# 3EWL1-200001_02.net
KiCad netlist of a schematic drawn in Altium Designer
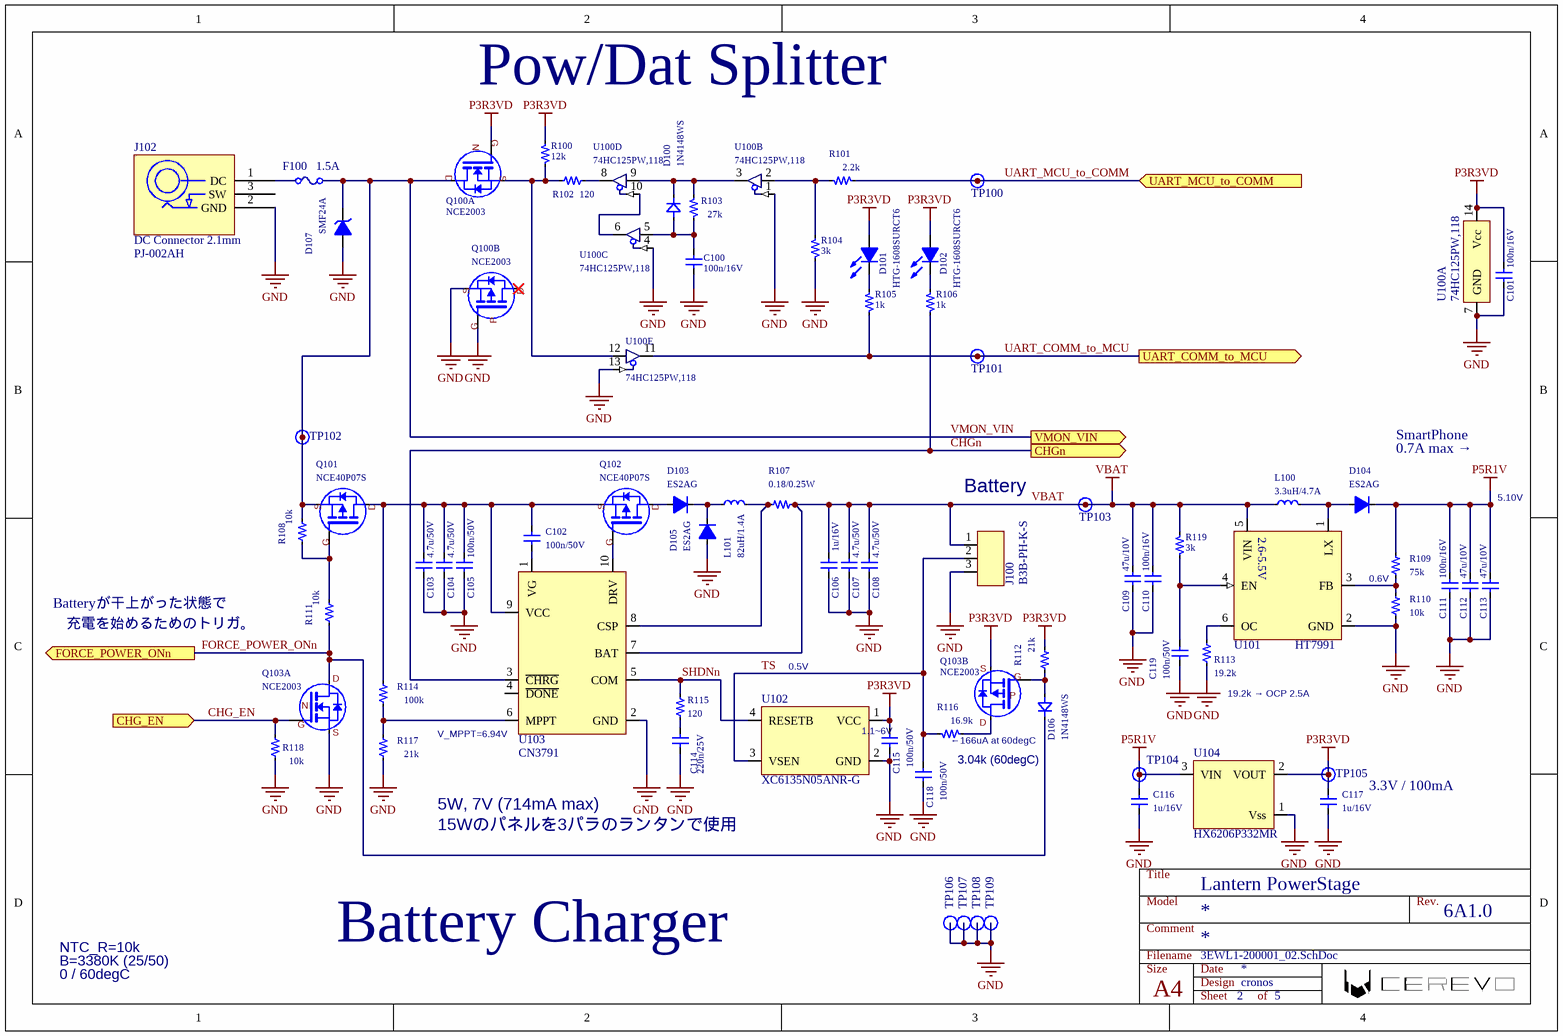
[diagram p0: 3EWL1-200001_02.SchDoc]

(export (version "E")
  (design (tool "Eeschema 10.0.6"))
  (components
    (comp (ref "C100")
      (value "100n/16V")
      (footprint "SC2-1.00X0.50A")
      (description "100n, 16V, X7R, 1005Size")
      (fields
        (field (name "MANUFACTURER") "TDK")
        (field (name "MANUFACTURER PART NUMBER") "C1005X5R1C104KT000N")
      )
      (libsource (lib "I_Lib_cronos_NewLayer") (part "C"))
    )
    (comp (ref "C101")
      (value "100n/16V")
      (footprint "SC2-1.00X0.50A")
      (description "100n, 16V, X7R, 1005Size")
      (fields
        (field (name "MANUFACTURER") "TDK")
        (field (name "MANUFACTURER PART NUMBER") "C1005X5R1C104KT000N")
      )
      (libsource (lib "I_Lib_cronos_NewLayer") (part "C"))
    )
    (comp (ref "C102")
      (value "100n/50V")
      (footprint "SC2-1.00X0.50A")
      (description "100n, 50V, X7R, 1005Size")
      (fields
        (field (name "MANUFACTURER") "Walsin")
        (field (name "MANUFACTURER PART NUMBER") "0402B104K500CT")
      )
      (libsource (lib "I_Lib_cronos_NewLayer") (part "C"))
    )
    (comp (ref "C103")
      (value "4.7u/50V")
      (footprint "SC2-3.20X1.60A")
      (description "4.7u/50V, X7R, 3216Size")
      (fields
        (field (name "MANUFACTURER") "Murata")
        (field (name "MANUFACTURER PART NUMBER") "GRM31CR71H475KA12L")
      )
      (libsource (lib "I_Lib_cronos_NewLayer") (part "C"))
    )
    (comp (ref "C104")
      (value "4.7u/50V")
      (footprint "SC2-3.20X1.60A")
      (description "4.7u/50V, X7R, 3216Size")
      (fields
        (field (name "MANUFACTURER") "Murata")
        (field (name "MANUFACTURER PART NUMBER") "GRM31CR71H475KA12L")
      )
      (libsource (lib "I_Lib_cronos_NewLayer") (part "C"))
    )
    (comp (ref "C105")
      (value "100n/50V")
      (footprint "SC2-1.00X0.50A")
      (description "100n, 50V, X7R, 1005Size")
      (fields
        (field (name "MANUFACTURER") "Walsin")
        (field (name "MANUFACTURER PART NUMBER") "0402B104K500CT")
      )
      (libsource (lib "I_Lib_cronos_NewLayer") (part "C"))
    )
    (comp (ref "C106")
      (value "1u/16V")
      (footprint "SC2-1.00X0.50A")
      (description "1u, 16V, X7R, 1005Size")
      (fields
        (field (name "MANUFACTURER") "Yageo")
        (field (name "MANUFACTURER PART NUMBER") "CC0805KKX7R7BB105")
      )
      (libsource (lib "I_Lib_cronos_NewLayer") (part "C"))
    )
    (comp (ref "C107")
      (value "4.7u/50V")
      (footprint "SC2-3.20X1.60A")
      (description "4.7u/50V, X7R, 3216Size")
      (fields
        (field (name "MANUFACTURER") "Murata")
        (field (name "MANUFACTURER PART NUMBER") "GRM31CR71H475KA12L")
      )
      (libsource (lib "I_Lib_cronos_NewLayer") (part "C"))
    )
    (comp (ref "C108")
      (value "4.7u/50V")
      (footprint "SC2-3.20X1.60A")
      (description "4.7u/50V, X7R, 3216Size")
      (fields
        (field (name "MANUFACTURER") "Murata")
        (field (name "MANUFACTURER PART NUMBER") "GRM31CR71H475KA12L")
      )
      (libsource (lib "I_Lib_cronos_NewLayer") (part "C"))
    )
    (comp (ref "C109")
      (value "47u/10V")
      (footprint "SC2-3.20X2.50A")
      (description "47u/10V, X7R, 3225Size")
      (fields
        (field (name "MANUFACTURER") "Murata")
        (field (name "MANUFACTURER PART NUMBER") "GRM32ER71A476KE15L")
      )
      (libsource (lib "I_Lib_cronos_NewLayer") (part "C"))
    )
    (comp (ref "C110")
      (value "100n/16V")
      (footprint "SC2-1.00X0.50A")
      (description "100n, 16V, X7R, 1005Size")
      (fields
        (field (name "MANUFACTURER") "TDK")
        (field (name "MANUFACTURER PART NUMBER") "C1005X5R1C104KT000N")
      )
      (libsource (lib "I_Lib_cronos_NewLayer") (part "C"))
    )
    (comp (ref "C111")
      (value "100n/16V")
      (footprint "SC2-1.00X0.50A")
      (description "100n, 16V, X7R, 1005Size")
      (fields
        (field (name "MANUFACTURER") "TDK")
        (field (name "MANUFACTURER PART NUMBER") "C1005X5R1C104KT000N")
      )
      (libsource (lib "I_Lib_cronos_NewLayer") (part "C"))
    )
    (comp (ref "C112")
      (value "47u/10V")
      (footprint "SC2-3.20X2.50A")
      (description "47u/10V, X7R, 3225Size")
      (fields
        (field (name "MANUFACTURER") "Murata")
        (field (name "MANUFACTURER PART NUMBER") "GRM32ER71A476KE15L")
      )
      (libsource (lib "I_Lib_cronos_NewLayer") (part "C"))
    )
    (comp (ref "C113")
      (value "47u/10V")
      (footprint "SC2-3.20X2.50A")
      (description "47u/10V, X7R, 3225Size")
      (fields
        (field (name "MANUFACTURER") "Murata")
        (field (name "MANUFACTURER PART NUMBER") "GRM32ER71A476KE15L")
      )
      (libsource (lib "I_Lib_cronos_NewLayer") (part "C"))
    )
    (comp (ref "C114")
      (value "220n/25V")
      (footprint "SC2-1.00X0.50A")
      (description "220n, 25V, X7R, 1005Size")
      (fields
        (field (name "MANUFACTURER") "Walsin")
        (field (name "MANUFACTURER PART NUMBER") "0402B224K250CT")
      )
      (libsource (lib "I_Lib_cronos_NewLayer") (part "C"))
    )
    (comp (ref "C115")
      (value "100n/50V")
      (footprint "SC2-1.00X0.50A")
      (description "100n, 50V, X7R, 1005Size")
      (fields
        (field (name "MANUFACTURER") "Walsin")
        (field (name "MANUFACTURER PART NUMBER") "0402B104K500CT")
      )
      (libsource (lib "I_Lib_cronos_NewLayer") (part "C"))
    )
    (comp (ref "C116")
      (value "1u/16V")
      (footprint "SC2-1.00X0.50A")
      (description "1u, 16V, X7R, 1005Size")
      (fields
        (field (name "MANUFACTURER") "Yageo")
        (field (name "MANUFACTURER PART NUMBER") "CC0805KKX7R7BB105")
      )
      (libsource (lib "I_Lib_cronos_NewLayer") (part "C"))
    )
    (comp (ref "C117")
      (value "1u/16V")
      (footprint "SC2-1.00X0.50A")
      (description "1u, 16V, X7R, 1005Size")
      (fields
        (field (name "MANUFACTURER") "Yageo")
        (field (name "MANUFACTURER PART NUMBER") "CC0805KKX7R7BB105")
      )
      (libsource (lib "I_Lib_cronos_NewLayer") (part "C"))
    )
    (comp (ref "C118")
      (value "100n/50V")
      (footprint "SC2-1.00X0.50A")
      (description "100n, 50V, X7R, 1005Size")
      (fields
        (field (name "MANUFACTURER") "Walsin")
        (field (name "MANUFACTURER PART NUMBER") "0402B104K500CT")
      )
      (libsource (lib "I_Lib_cronos_NewLayer") (part "C"))
    )
    (comp (ref "C119")
      (value "100n/50V")
      (footprint "SC2-1.00X0.50A")
      (description "100n, 50V, X7R, 1005Size")
      (fields
        (field (name "MANUFACTURER") "Walsin")
        (field (name "MANUFACTURER PART NUMBER") "0402B104K500CT")
      )
      (libsource (lib "I_Lib_cronos_NewLayer") (part "C"))
    )
    (comp (ref "D100")
      (value "1N4148WS")
      (footprint "SD2-1.7X1.25A")
      (description "Diode Signal 75V 150mA 1712")
      (fields (field (name "MANUFACTURER") "Fairchild Semiconductor"))
      (libsource (lib "I_Lib_cronos_NewLayer") (part "1N4148WS"))
    )
    (comp (ref "D101")
      (value "HTG-1608SURCT6")
      (footprint "SOD-523F_CAPM3216X18N")
      (fields (field (name "MANUFACTURER") "HTGLight"))
      (libsource (lib "I_Lib_cronos") (part "Diode_LED"))
    )
    (comp (ref "D102")
      (value "HTG-1608SURCT6")
      (footprint "SOD-523F_CAPM3216X18N")
      (fields (field (name "MANUFACTURER") "HTGLight"))
      (libsource (lib "I_Lib_cronos") (part "Diode_LED"))
    )
    (comp (ref "D103")
      (value "ES2AG")
      (footprint "diodes_SMA")
      (description "50V, 2A, Vf_2A=1V, 35nSec, SMA")
      (fields (field (name "MANUFACTURER") "Shikues"))
      (libsource (lib "I_Lib_cronos_NewLayer") (part "Diode_switching"))
    )
    (comp (ref "D104")
      (value "ES2AG")
      (footprint "diodes_SMA")
      (description "50V, 2A, Vf_2A=1V, 35nSec, SMA")
      (fields (field (name "MANUFACTURER") "Shikues"))
      (libsource (lib "I_Lib_cronos_NewLayer") (part "Diode_switching"))
    )
    (comp (ref "D105")
      (value "ES2AG")
      (footprint "diodes_SMA")
      (description "50V, 2A, Vf_2A=1V, 35nSec, SMA")
      (fields (field (name "MANUFACTURER") "Shikues"))
      (libsource (lib "I_Lib_cronos_NewLayer") (part "Diode_switching"))
    )
    (comp (ref "D106")
      (value "1N4148WS")
      (footprint "SD2-1.7X1.25A")
      (description "Diode Signal 75V 150mA 1712")
      (fields (field (name "MANUFACTURER") "Fairchild Semiconductor"))
      (libsource (lib "I_Lib_cronos_NewLayer") (part "1N4148WS"))
    )
    (comp (ref "D107")
      (value "SMF24A")
      (footprint "SOD-123")
      (fields (field (name "MANUFACTURER") "DOWO"))
      (libsource (lib "I_Lib_cronos_NewLayer") (part "Diode_Zenner"))
    )
    (comp (ref "F100")
      (value "1.5A")
      (footprint "SR2-1.60X0.80A")
      (description "1.5A, 32V, 1608Size")
      (fields
        (field (name "MANUFACTURER") "Shenzhen lanson Elec")
        (field (name "MANUFACTURER PART NUMBER") "06H1150D")
      )
      (libsource (lib "I_Lib_cronos_NewLayer") (part "Fuse"))
    )
    (comp (ref "J100")
      (value "B3B-PH-K-S")
      (footprint "B3B-PH-K-S")
      (description "PH 3pin 2mm pitch")
      (fields (field (name "MANUFACTURER") "JST"))
      (libsource (lib "I_Lib_cronos_NewLayer") (part "Con3"))
    )
    (comp (ref "J102")
      (value "DC Connector 2.1mm")
      (footprint "Connector_PJ-002AH")
      (description "Connector - DC 12V")
      (fields (field (name "MANUFACTURER") "CUI Inc.") (field (name "MANUFACTURER PART NUMBER") "PJ-002AH"))
      (libsource (lib "I_Lib_cronos_NewLayer") (part "Connector - DC_PJ-002AH"))
    )
    (comp (ref "L100")
      (value "3.3uH/4.7A")
      (footprint "VLC6045")
      (description "3.3uH, 4.7A, 6x6x4.5mm")
      (fields (field (name "MANUFACTURER") "TDK") (field (name "MANUFACTURER PART NUMBER") "VLC6045T-3R3N"))
      (libsource (lib "I_Lib_cronos_NewLayer") (part "L"))
    )
    (comp (ref "L101")
      (value "82uH/1.4A")
      (footprint "SCDS125T-820M-N")
      (description "82uH, 1.4A, 12.5x12.5x6mm")
      (fields
        (field (name "MANUFACTURER") "Chilisin Elec")
        (field (name "MANUFACTURER PART NUMBER") "SCDS125T-820M-N")
      )
      (libsource (lib "I_Lib_cronos_NewLayer") (part "L"))
    )
    (comp (ref "Q100")
      (value "NCE2003")
      (footprint "SOT23-6")
      (description "N(20V, 55mohm, Vgs(th)=1.2V ), P(-20V, 100mohm, Vgs(th)=-1V), SOT23-6")
      (fields (field (name "MANUFACTURER") "ncepower"))
      (libsource (lib "I_Lib_cronos_NewLayer") (part "NCE2003"))
    )
    (comp (ref "Q101")
      (value "NCE40P07S")
      (footprint "SOIC127P610X104_HS-9M")
      (description "-40V, -6.2A, 30mohm")
      (fields (field (name "MANUFACTURER") "Wuxi NCE Power Semiconductor"))
      (libsource (lib "I_Lib_cronos_NewLayer") (part "Pch_MOSFET"))
    )
    (comp (ref "Q102")
      (value "NCE40P07S")
      (footprint "SOIC127P610X104_HS-9M")
      (description "-40V, -6.2A, 30mohm")
      (fields (field (name "MANUFACTURER") "Wuxi NCE Power Semiconductor"))
      (libsource (lib "I_Lib_cronos_NewLayer") (part "Pch_MOSFET"))
    )
    (comp (ref "Q103")
      (value "NCE2003")
      (footprint "SOT23-6")
      (description "N(20V, 55mohm, Vgs(th)=1.2V ), P(-20V, 100mohm, Vgs(th)=-1V), SOT23-6")
      (fields (field (name "MANUFACTURER") "ncepower"))
      (libsource (lib "I_Lib_cronos_NewLayer") (part "NCE2003"))
    )
    (comp (ref "R100")
      (value "12k")
      (footprint "SR2-1.00X0.50A")
      (description "12k, 1%, 1005Size")
      (fields
        (field (name "MANUFACTURER") "YAGEO")
        (field (name "MANUFACTURER PART NUMBER") "RC0402FR-0712KL")
      )
      (libsource (lib "I_Lib_cronos_NewLayer") (part "R"))
    )
    (comp (ref "R101")
      (value "2.2k")
      (footprint "SR2-1.00X0.50A")
      (description "2.2k, 1%, 1005Size")
      (fields
        (field (name "MANUFACTURER") "YAGEO")
        (field (name "MANUFACTURER PART NUMBER") "RC0402FR-072K2RL")
      )
      (libsource (lib "I_Lib_cronos_NewLayer") (part "R"))
    )
    (comp (ref "R102")
      (value "120")
      (footprint "SR2-1.00X0.50A")
      (description "120, 1%, 1005Size")
      (fields
        (field (name "MANUFACTURER") "YAGEO")
        (field (name "MANUFACTURER PART NUMBER") "RC0402FR-07120RL")
      )
      (libsource (lib "I_Lib_cronos_NewLayer") (part "R"))
    )
    (comp (ref "R103")
      (value "27k")
      (footprint "SR2-1.00X0.50A")
      (description "27k, 1%, 1005Size")
      (fields
        (field (name "MANUFACTURER") "YAGEO")
        (field (name "MANUFACTURER PART NUMBER") "RC0402FR-0727KL")
      )
      (libsource (lib "I_Lib_cronos_NewLayer") (part "R"))
    )
    (comp (ref "R104")
      (value "3k")
      (footprint "SR2-1.00X0.50A")
      (description "3k, 1%, 1005Size")
      (fields
        (field (name "MANUFACTURER") "YAGEO")
        (field (name "MANUFACTURER PART NUMBER") "RC0402FR-073KL")
      )
      (libsource (lib "I_Lib_cronos_NewLayer") (part "R"))
    )
    (comp (ref "R105")
      (value "1k")
      (footprint "SR2-1.00X0.50A")
      (description "Rsisiter 2pin")
      (fields
        (field (name "MANUFACTURER") "Yageo")
        (field (name "MANUFACTURER PART NUMBER") "RC0402FR-071KL")
      )
      (libsource (lib "I_Lib_cronos") (part "R"))
    )
    (comp (ref "R106")
      (value "1k")
      (footprint "SR2-1.00X0.50A")
      (description "Rsisiter 2pin")
      (fields
        (field (name "MANUFACTURER") "Yageo")
        (field (name "MANUFACTURER PART NUMBER") "RC0402FR-071KL")
      )
      (libsource (lib "I_Lib_cronos") (part "R"))
    )
    (comp (ref "R107")
      (value "0.18/0.25W")
      (footprint "SR2-3.20X1.60A")
      (description "0.18, 0.25W, 1%, 800ppm")
      (fields
        (field (name "MANUFACTURER") "UNI-ROYAL")
        (field (name "MANUFACTURER PART NUMBER") "1206W4F180LT5E")
      )
      (libsource (lib "I_Lib_cronos_NewLayer") (part "R"))
    )
    (comp (ref "R108")
      (value "10k")
      (footprint "SR2-1.00X0.50A")
      (fields
        (field (name "MANUFACTURER") "YAGEO")
        (field (name "MANUFACTURER PART NUMBER") "RC0402FR-0710KL")
      )
      (libsource (lib "I_Lib_cronos_NewLayer") (part "R"))
    )
    (comp (ref "R109")
      (value "75k")
      (footprint "SR2-1.00X0.50A")
      (fields
        (field (name "MANUFACTURER") "YAGEO")
        (field (name "MANUFACTURER PART NUMBER") "RC0402FR-0775KL")
      )
      (libsource (lib "I_Lib_cronos_NewLayer") (part "R"))
    )
    (comp (ref "R110")
      (value "10k")
      (footprint "SR2-1.00X0.50A")
      (fields
        (field (name "MANUFACTURER") "YAGEO")
        (field (name "MANUFACTURER PART NUMBER") "RC0402FR-0710KL")
      )
      (libsource (lib "I_Lib_cronos_NewLayer") (part "R"))
    )
    (comp (ref "R111")
      (value "10k")
      (footprint "SR2-1.00X0.50A")
      (fields
        (field (name "MANUFACTURER") "YAGEO")
        (field (name "MANUFACTURER PART NUMBER") "RC0402FR-0710KL")
      )
      (libsource (lib "I_Lib_cronos_NewLayer") (part "R"))
    )
    (comp (ref "R112")
      (value "21k")
      (footprint "SR2-1.00X0.50A")
      (description "21k, 1%, 1005Size")
      (fields
        (field (name "MANUFACTURER") "YAGEO")
        (field (name "MANUFACTURER PART NUMBER") "RC0402FR-0721KL")
      )
      (libsource (lib "I_Lib_cronos_NewLayer") (part "R"))
    )
    (comp (ref "R113")
      (value "19.2k")
      (footprint "SR2-1.00X0.50A")
      (fields
        (field (name "MANUFACTURER") "YAGEO")
        (field (name "MANUFACTURER PART NUMBER") "RC0402FR-0719K2L")
      )
      (libsource (lib "I_Lib_cronos_NewLayer") (part "R"))
    )
    (comp (ref "R114")
      (value "100k")
      (footprint "SR2-1.00X0.50A")
      (description "100k, 1%, 1005Size")
      (fields
        (field (name "MANUFACTURER") "YAGEO")
        (field (name "MANUFACTURER PART NUMBER") "RC0402FR-07100KL")
      )
      (libsource (lib "I_Lib_cronos_NewLayer") (part "R"))
    )
    (comp (ref "R115")
      (value "120")
      (footprint "SR2-1.00X0.50A")
      (description "120, 1%, 1005Size")
      (fields
        (field (name "MANUFACTURER") "YAGEO")
        (field (name "MANUFACTURER PART NUMBER") "RC0402FR-07120RL")
      )
      (libsource (lib "I_Lib_cronos_NewLayer") (part "R"))
    )
    (comp (ref "R116")
      (value "16.9k")
      (footprint "SR2-1.00X0.50A")
      (description "16.9k, 1%, 1005Size")
      (fields
        (field (name "MANUFACTURER") "YAGEO")
        (field (name "MANUFACTURER PART NUMBER") "RC0402FR-0716K9L")
      )
      (libsource (lib "I_Lib_cronos_NewLayer") (part "R"))
    )
    (comp (ref "R117")
      (value "21k")
      (footprint "SR2-1.00X0.50A")
      (description "21k, 1%, 1005Size")
      (fields
        (field (name "MANUFACTURER") "YAGEO")
        (field (name "MANUFACTURER PART NUMBER") "RC0402FR-0721KL")
      )
      (libsource (lib "I_Lib_cronos_NewLayer") (part "R"))
    )
    (comp (ref "R118")
      (value "10k")
      (footprint "SR2-1.00X0.50A")
      (fields
        (field (name "MANUFACTURER") "YAGEO")
        (field (name "MANUFACTURER PART NUMBER") "RC0402FR-0710KL")
      )
      (libsource (lib "I_Lib_cronos_NewLayer") (part "R"))
    )
    (comp (ref "R119")
      (value "3k")
      (footprint "SR2-1.00X0.50A")
      (description "3k, 1%, 1005Size")
      (fields
        (field (name "MANUFACTURER") "YAGEO")
        (field (name "MANUFACTURER PART NUMBER") "RC0402FR-073KL")
      )
      (libsource (lib "I_Lib_cronos_NewLayer") (part "R"))
    )
    (comp (ref "TP100")
      (value "TP")
      (footprint "1.0mmTH")
      (libsource (lib "I_Lib_cronos_NewLayer") (part "TP"))
    )
    (comp (ref "TP101")
      (value "TP")
      (footprint "1.0mmTH")
      (libsource (lib "I_Lib_cronos_NewLayer") (part "TP"))
    )
    (comp (ref "TP102")
      (value "TP")
      (footprint "1.0mmTH")
      (libsource (lib "I_Lib_cronos_NewLayer") (part "TP"))
    )
    (comp (ref "TP103")
      (value "TP")
      (footprint "1.0mmTH")
      (libsource (lib "I_Lib_cronos_NewLayer") (part "TP"))
    )
    (comp (ref "TP104")
      (value "TP")
      (footprint "1.0mmTH")
      (libsource (lib "I_Lib_cronos_NewLayer") (part "TP"))
    )
    (comp (ref "TP105")
      (value "TP")
      (footprint "1.0mmTH")
      (libsource (lib "I_Lib_cronos_NewLayer") (part "TP"))
    )
    (comp (ref "TP106")
      (value "TP")
      (footprint "1.0mmTH")
      (libsource (lib "I_Lib_cronos_NewLayer") (part "TP"))
    )
    (comp (ref "TP107")
      (value "TP")
      (footprint "1.0mmTH")
      (libsource (lib "I_Lib_cronos_NewLayer") (part "TP"))
    )
    (comp (ref "TP108")
      (value "TP")
      (footprint "1.0mmTH")
      (libsource (lib "I_Lib_cronos_NewLayer") (part "TP"))
    )
    (comp (ref "TP109")
      (value "TP")
      (footprint "1.0mmTH")
      (libsource (lib "I_Lib_cronos_NewLayer") (part "TP"))
    )
    (comp (ref "U100")
      (value "74HC125PW,118")
      (footprint "TSSOP14_e=0.65")
      (description "3-State Quad Buffer")
      (fields (field (name "MANUFACTURER") "NXP"))
      (libsource (lib "") (part "74HC125_2"))
    )
    (comp (ref "U101")
      (value "HT7991")
      (footprint "SOT23-6")
      (description "boost, 2.6-5.5V, 2.5A, 1MHz")
      (fields (field (name "MANUFACTURER") "Holtek"))
      (libsource (lib "I_Lib_cronos_NewLayer") (part "HT7991"))
    )
    (comp (ref "U102")
      (value "XC6135N05ANR-G")
      (footprint "XC6135N05ANR-G")
      (description "Voltage Detector Vth=0.5V")
      (fields (field (name "MANUFACTURER") "TOREX"))
      (libsource (lib "I_Lib_cronos_NewLayer") (part "XC6135N05ANR-G"))
    )
    (comp (ref "U103")
      (value "CN3791")
      (footprint "CN3791")
      (description "8:1 Multiplexer")
      (fields (field (name "MANUFACTURER") "CONSONANCE"))
      (libsource (lib "I_Lib_cronos_NewLayer") (part "CN3791"))
    )
    (comp (ref "U104")
      (value "HX6206P332MR")
      (footprint "SOT23-3")
      (description "3.3V 100mA SOT-23")
      (fields (field (name "MANUFACTURER") "hengjiaxing"))
      (libsource (lib "I_Lib_cronos_NewLayer") (part "HX6206P332MR"))
    )
  )
  (nets
    (net (code "1") (name "/CHG_EN") (class "Default")
      (node (ref "Q103") (pin "1") (pinfunction "N_G_1") (pintype "passive"))
      (node (ref "R118") (pin "1") (pinfunction "1_1") (pintype "passive"))
    )
    (net (code "2") (name "/CHGn") (class "Default")
      (node (ref "R106") (pin "1") (pinfunction "1_1") (pintype "passive"))
      (node (ref "U103") (pin "3") (pinfunction "~{CHRG}_3") (pintype "passive"))
    )
    (net (code "3") (name "/FORCE_POWER_ONn") (class "Default")
      (node (ref "D106") (pin "K") (pinfunction "K_K") (pintype "passive"))
      (node (ref "Q103") (pin "6") (pinfunction "N_D_6") (pintype "passive"))
      (node (ref "R111") (pin "2") (pinfunction "2_2") (pintype "passive"))
    )
    (net (code "4") (name "/SHDNn") (class "Default")
      (node (ref "R115") (pin "2") (pinfunction "2_2") (pintype "passive"))
      (node (ref "U102") (pin "4") (pinfunction "RESETB_4") (pintype "open_collector"))
      (node (ref "U103") (pin "5") (pinfunction "COM_5") (pintype "passive"))
    )
    (net (code "5") (name "/TS") (class "Default")
      (node (ref "C118") (pin "1") (pinfunction "1_1") (pintype "passive"))
      (node (ref "J100") (pin "2") (pinfunction "2_2") (pintype "passive"))
      (node (ref "R116") (pin "2") (pinfunction "2_2") (pintype "passive"))
      (node (ref "U102") (pin "3") (pinfunction "VSEN_3") (pintype "passive"))
    )
    (net (code "6") (name "/UART_COMM_to_MCU") (class "Default")
      (node (ref "R105") (pin "1") (pinfunction "1_1") (pintype "passive"))
      (node (ref "TP101") (pin "1") (pinfunction "TP1_1") (pintype "passive"))
      (node (ref "U100") (pin "11") (pinfunction "4Y_11") (pintype "passive"))
    )
    (net (code "7") (name "/UART_MCU_to_COMM") (class "Default")
      (node (ref "R101") (pin "1") (pinfunction "1_1") (pintype "passive"))
      (node (ref "TP100") (pin "1") (pinfunction "TP1_1") (pintype "passive"))
    )
    (net (code "8") (name "/VMON_VIN") (class "Default")
      (node (ref "D107") (pin "C") (pinfunction "C_C") (pintype "passive"))
      (node (ref "F100") (pin "2") (pinfunction "2_2") (pintype "passive"))
      (node (ref "Q100") (pin "6") (pinfunction "N_D_6") (pintype "passive"))
      (node (ref "Q101") (pin "2") (pinfunction "S_2") (pintype "passive"))
      (node (ref "R108") (pin "1") (pinfunction "1_1") (pintype "passive"))
      (node (ref "TP102") (pin "1") (pinfunction "TP1_1") (pintype "passive"))
    )
    (net (code "9") (name "GND") (class "Default")
      (node (ref "C100") (pin "2") (pinfunction "2_2") (pintype "passive"))
      (node (ref "C101") (pin "2") (pinfunction "2_2") (pintype "passive"))
      (node (ref "C103") (pin "1") (pinfunction "1_1") (pintype "passive"))
      (node (ref "C104") (pin "1") (pinfunction "1_1") (pintype "passive"))
      (node (ref "C105") (pin "2") (pinfunction "2_2") (pintype "passive"))
      (node (ref "C106") (pin "2") (pinfunction "2_2") (pintype "passive"))
      (node (ref "C107") (pin "1") (pinfunction "1_1") (pintype "passive"))
      (node (ref "C108") (pin "1") (pinfunction "1_1") (pintype "passive"))
      (node (ref "C109") (pin "1") (pinfunction "1_1") (pintype "passive"))
      (node (ref "C110") (pin "2") (pinfunction "2_2") (pintype "passive"))
      (node (ref "C111") (pin "2") (pinfunction "2_2") (pintype "passive"))
      (node (ref "C112") (pin "1") (pinfunction "1_1") (pintype "passive"))
      (node (ref "C113") (pin "1") (pinfunction "1_1") (pintype "passive"))
      (node (ref "C114") (pin "1") (pinfunction "1_1") (pintype "passive"))
      (node (ref "C115") (pin "2") (pinfunction "2_2") (pintype "passive"))
      (node (ref "C116") (pin "2") (pinfunction "2_2") (pintype "passive"))
      (node (ref "C117") (pin "2") (pinfunction "2_2") (pintype "passive"))
      (node (ref "C118") (pin "2") (pinfunction "2_2") (pintype "passive"))
      (node (ref "C119") (pin "2") (pinfunction "2_2") (pintype "passive"))
      (node (ref "D105") (pin "A") (pinfunction "A_A") (pintype "passive"))
      (node (ref "D107") (pin "A") (pinfunction "A_A") (pintype "passive"))
      (node (ref "J100") (pin "3") (pinfunction "3_3") (pintype "passive"))
      (node (ref "J102") (pin "2") (pinfunction "GND_2") (pintype "power_in"))
      (node (ref "Q100") (pin "2") (pinfunction "P_S_2") (pintype "passive"))
      (node (ref "Q100") (pin "3") (pinfunction "P_G_3") (pintype "passive"))
      (node (ref "Q103") (pin "5") (pinfunction "N_S_5") (pintype "passive"))
      (node (ref "R104") (pin "2") (pinfunction "2_2") (pintype "passive"))
      (node (ref "R110") (pin "2") (pinfunction "2_2") (pintype "passive"))
      (node (ref "R113") (pin "2") (pinfunction "2_2") (pintype "passive"))
      (node (ref "R117") (pin "2") (pinfunction "2_2") (pintype "passive"))
      (node (ref "R118") (pin "2") (pinfunction "2_2") (pintype "passive"))
      (node (ref "TP106") (pin "1") (pinfunction "TP1_1") (pintype "passive"))
      (node (ref "TP107") (pin "1") (pinfunction "TP1_1") (pintype "passive"))
      (node (ref "TP108") (pin "1") (pinfunction "TP1_1") (pintype "passive"))
      (node (ref "TP109") (pin "1") (pinfunction "TP1_1") (pintype "passive"))
      (node (ref "U100") (pin "1") (pinfunction "1OE_1") (pintype "input"))
      (node (ref "U100") (pin "13") (pinfunction "4OE_13") (pintype "input"))
      (node (ref "U100") (pin "4") (pinfunction "2OE_4") (pintype "input"))
      (node (ref "U100") (pin "7") (pinfunction "GND_7") (pintype "power_in"))
      (node (ref "U101") (pin "2") (pinfunction "GND_2") (pintype "power_in"))
      (node (ref "U102") (pin "2") (pinfunction "GND_2") (pintype "power_in"))
      (node (ref "U103") (pin "2") (pinfunction "GND_2") (pintype "power_in"))
      (node (ref "U104") (pin "1") (pinfunction "Vss_1") (pintype "power_in"))
    )
    (net (code "10") (name "Net-(C114-Pad2)") (class "Default")
      (node (ref "C114") (pin "2") (pinfunction "2_2") (pintype "passive"))
      (node (ref "R115") (pin "1") (pinfunction "1_1") (pintype "passive"))
    )
    (net (code "11") (name "Net-(D101-2)") (class "Default")
      (node (ref "D101") (pin "C") (pinfunction "2_C") (pintype "passive"))
      (node (ref "R105") (pin "2") (pinfunction "2_2") (pintype "passive"))
    )
    (net (code "12") (name "Net-(D102-2)") (class "Default")
      (node (ref "D102") (pin "C") (pinfunction "2_C") (pintype "passive"))
      (node (ref "R106") (pin "2") (pinfunction "2_2") (pintype "passive"))
    )
    (net (code "13") (name "Net-(D103-PadC)") (class "Default")
      (node (ref "D103") (pin "C") (pinfunction "C_C") (pintype "passive"))
      (node (ref "D105") (pin "C") (pinfunction "C_C") (pintype "passive"))
      (node (ref "L101") (pin "1") (pinfunction "1_1") (pintype "passive"))
    )
    (net (code "14") (name "Net-(J102-DC)") (class "Default")
      (node (ref "F100") (pin "1") (pinfunction "1_1") (pintype "passive"))
      (node (ref "J102") (pin "1") (pinfunction "DC_1") (pintype "passive"))
    )
    (net (code "15") (name "Net-(Q100A-N_S)") (class "Default")
      (node (ref "Q100") (pin "5") (pinfunction "N_S_5") (pintype "passive"))
      (node (ref "R100") (pin "2") (pinfunction "2_2") (pintype "passive"))
      (node (ref "R102") (pin "2") (pinfunction "2_2") (pintype "passive"))
      (node (ref "U100") (pin "12") (pinfunction "4A_12") (pintype "passive"))
    )
    (net (code "16") (name "Net-(Q101-D)") (class "Default")
      (node (ref "C102") (pin "1") (pinfunction "1_1") (pintype "passive"))
      (node (ref "C103") (pin "2") (pinfunction "2_2") (pintype "passive"))
      (node (ref "C104") (pin "2") (pinfunction "2_2") (pintype "passive"))
      (node (ref "C105") (pin "1") (pinfunction "1_1") (pintype "passive"))
      (node (ref "Q101") (pin "3") (pinfunction "D_3") (pintype "passive"))
      (node (ref "Q102") (pin "2") (pinfunction "S_2") (pintype "passive"))
      (node (ref "R114") (pin "1") (pinfunction "1_1") (pintype "passive"))
      (node (ref "U103") (pin "9") (pinfunction "VCC_9") (pintype "power_in"))
    )
    (net (code "17") (name "Net-(Q101-G)") (class "Default")
      (node (ref "Q101") (pin "1") (pinfunction "G_1") (pintype "passive"))
      (node (ref "R108") (pin "2") (pinfunction "2_2") (pintype "passive"))
      (node (ref "R111") (pin "1") (pinfunction "1_1") (pintype "passive"))
    )
    (net (code "18") (name "Net-(Q102-D)") (class "Default")
      (node (ref "D103") (pin "A") (pinfunction "A_A") (pintype "passive"))
      (node (ref "Q102") (pin "3") (pinfunction "D_3") (pintype "passive"))
    )
    (net (code "19") (name "Net-(Q102-G)") (class "Default")
      (node (ref "Q102") (pin "1") (pinfunction "G_1") (pintype "passive"))
      (node (ref "U103") (pin "10") (pinfunction "DRV_10") (pintype "passive"))
    )
    (net (code "20") (name "Net-(Q103B-P_D)") (class "Default")
      (node (ref "Q103") (pin "4") (pinfunction "P_D_4") (pintype "passive"))
      (node (ref "R116") (pin "1") (pinfunction "1_1") (pintype "passive"))
    )
    (net (code "21") (name "Net-(Q103B-P_G)") (class "Default")
      (node (ref "D106") (pin "A") (pinfunction "A_A") (pintype "passive"))
      (node (ref "Q103") (pin "3") (pinfunction "P_G_3") (pintype "passive"))
      (node (ref "R112") (pin "2") (pinfunction "2_2") (pintype "passive"))
    )
    (net (code "22") (name "Net-(U100B-1A)") (class "Default")
      (node (ref "R101") (pin "2") (pinfunction "2_2") (pintype "passive"))
      (node (ref "R104") (pin "1") (pinfunction "1_1") (pintype "passive"))
      (node (ref "U100") (pin "2") (pinfunction "1A_2") (pintype "passive"))
    )
    (net (code "23") (name "Net-(U100B-1Y)") (class "Default")
      (node (ref "D100") (pin "K") (pinfunction "K_K") (pintype "passive"))
      (node (ref "R103") (pin "1") (pinfunction "1_1") (pintype "passive"))
      (node (ref "U100") (pin "3") (pinfunction "1Y_3") (pintype "passive"))
      (node (ref "U100") (pin "9") (pinfunction "3A_9") (pintype "passive"))
    )
    (net (code "24") (name "Net-(U100C-2A)") (class "Default")
      (node (ref "C100") (pin "1") (pinfunction "1_1") (pintype "passive"))
      (node (ref "D100") (pin "A") (pinfunction "A_A") (pintype "passive"))
      (node (ref "R103") (pin "2") (pinfunction "2_2") (pintype "passive"))
      (node (ref "U100") (pin "5") (pinfunction "2A_5") (pintype "passive"))
    )
    (net (code "25") (name "Net-(U100C-2Y)") (class "Default")
      (node (ref "U100") (pin "10") (pinfunction "3OE_10") (pintype "input"))
      (node (ref "U100") (pin "6") (pinfunction "2Y_6") (pintype "passive"))
    )
    (net (code "26") (name "Net-(U100D-3Y)") (class "Default")
      (node (ref "R102") (pin "1") (pinfunction "1_1") (pintype "passive"))
      (node (ref "U100") (pin "8") (pinfunction "3Y_8") (pintype "passive"))
    )
    (net (code "27") (name "Net-(U101-EN)") (class "Default")
      (node (ref "C119") (pin "1") (pinfunction "1_1") (pintype "passive"))
      (node (ref "R119") (pin "2") (pinfunction "2_2") (pintype "passive"))
      (node (ref "U101") (pin "4") (pinfunction "EN_4") (pintype "input"))
    )
    (net (code "28") (name "Net-(U101-FB)") (class "Default")
      (node (ref "R109") (pin "2") (pinfunction "2_2") (pintype "passive"))
      (node (ref "R110") (pin "1") (pinfunction "1_1") (pintype "passive"))
      (node (ref "U101") (pin "3") (pinfunction "FB_3") (pintype "passive"))
    )
    (net (code "29") (name "Net-(U101-LX)") (class "Default")
      (node (ref "D104") (pin "A") (pinfunction "A_A") (pintype "passive"))
      (node (ref "L100") (pin "2") (pinfunction "2_2") (pintype "passive"))
      (node (ref "U101") (pin "1") (pinfunction "LX_1") (pintype "passive"))
    )
    (net (code "30") (name "Net-(U101-OC)") (class "Default")
      (node (ref "R113") (pin "1") (pinfunction "1_1") (pintype "passive"))
      (node (ref "U101") (pin "6") (pinfunction "OC_6") (pintype "passive"))
    )
    (net (code "31") (name "Net-(U103-CSP)") (class "Default")
      (node (ref "L101") (pin "2") (pinfunction "2_2") (pintype "passive"))
      (node (ref "R107") (pin "1") (pinfunction "1_1") (pintype "passive"))
      (node (ref "U103") (pin "8") (pinfunction "CSP_8") (pintype "passive"))
    )
    (net (code "32") (name "Net-(U103-MPPT)") (class "Default")
      (node (ref "R114") (pin "2") (pinfunction "2_2") (pintype "passive"))
      (node (ref "R117") (pin "1") (pinfunction "1_1") (pintype "passive"))
      (node (ref "U103") (pin "6") (pinfunction "MPPT_6") (pintype "passive"))
    )
    (net (code "33") (name "Net-(U103-VG)") (class "Default")
      (node (ref "C102") (pin "2") (pinfunction "2_2") (pintype "passive"))
      (node (ref "U103") (pin "1") (pinfunction "VG_1") (pintype "passive"))
    )
    (net (code "34") (name "P3R3VD") (class "Default")
      (node (ref "C101") (pin "1") (pinfunction "1_1") (pintype "passive"))
      (node (ref "C115") (pin "1") (pinfunction "1_1") (pintype "passive"))
      (node (ref "C117") (pin "1") (pinfunction "1_1") (pintype "passive"))
      (node (ref "D101") (pin "A") (pinfunction "1_A") (pintype "passive"))
      (node (ref "D102") (pin "A") (pinfunction "1_A") (pintype "passive"))
      (node (ref "Q100") (pin "1") (pinfunction "N_G_1") (pintype "passive"))
      (node (ref "Q103") (pin "2") (pinfunction "P_S_2") (pintype "passive"))
      (node (ref "R100") (pin "1") (pinfunction "1_1") (pintype "passive"))
      (node (ref "R112") (pin "1") (pinfunction "1_1") (pintype "passive"))
      (node (ref "TP105") (pin "1") (pinfunction "TP1_1") (pintype "passive"))
      (node (ref "U100") (pin "14") (pinfunction "Vcc_14") (pintype "power_in"))
      (node (ref "U102") (pin "1") (pinfunction "VCC_1") (pintype "power_in"))
      (node (ref "U104") (pin "2") (pinfunction "VOUT_2") (pintype "power_in"))
    )
    (net (code "35") (name "P5R1V") (class "Default")
      (node (ref "C111") (pin "1") (pinfunction "1_1") (pintype "passive"))
      (node (ref "C112") (pin "2") (pinfunction "2_2") (pintype "passive"))
      (node (ref "C113") (pin "2") (pinfunction "2_2") (pintype "passive"))
      (node (ref "C116") (pin "1") (pinfunction "1_1") (pintype "passive"))
      (node (ref "D104") (pin "C") (pinfunction "C_C") (pintype "passive"))
      (node (ref "R109") (pin "1") (pinfunction "1_1") (pintype "passive"))
      (node (ref "TP104") (pin "1") (pinfunction "TP1_1") (pintype "passive"))
      (node (ref "U104") (pin "3") (pinfunction "VIN_3") (pintype "power_in"))
    )
    (net (code "36") (name "VBAT") (class "Default")
      (node (ref "C106") (pin "1") (pinfunction "1_1") (pintype "passive"))
      (node (ref "C107") (pin "2") (pinfunction "2_2") (pintype "passive"))
      (node (ref "C108") (pin "2") (pinfunction "2_2") (pintype "passive"))
      (node (ref "C109") (pin "2") (pinfunction "2_2") (pintype "passive"))
      (node (ref "C110") (pin "1") (pinfunction "1_1") (pintype "passive"))
      (node (ref "J100") (pin "1") (pinfunction "1_1") (pintype "passive"))
      (node (ref "L100") (pin "1") (pinfunction "1_1") (pintype "passive"))
      (node (ref "R107") (pin "2") (pinfunction "2_2") (pintype "passive"))
      (node (ref "R119") (pin "1") (pinfunction "1_1") (pintype "passive"))
      (node (ref "TP103") (pin "1") (pinfunction "TP1_1") (pintype "passive"))
      (node (ref "U101") (pin "5") (pinfunction "VIN_5") (pintype "passive"))
      (node (ref "U103") (pin "7") (pinfunction "BAT_7") (pintype "passive"))
    )
    (net (code "37") (name "unconnected-(J102-SW-Pad3)") (class "Default")
      (node (ref "J102") (pin "3") (pinfunction "SW_3") (pintype "power_in"))
    )
    (net (code "38") (name "unconnected-(Q100B-P_D-Pad4)") (class "Default")
      (node (ref "Q100") (pin "4") (pinfunction "P_D_4") (pintype "passive+no_connect"))
    )
    (net (code "39") (name "unconnected-(U103-~{DONE}-Pad4)") (class "Default")
      (node (ref "U103") (pin "4") (pinfunction "~{DONE}_4") (pintype "passive"))
    )
  )
)
